# Sheet1.net
KiCad netlist of a schematic drawn in Altium Designer
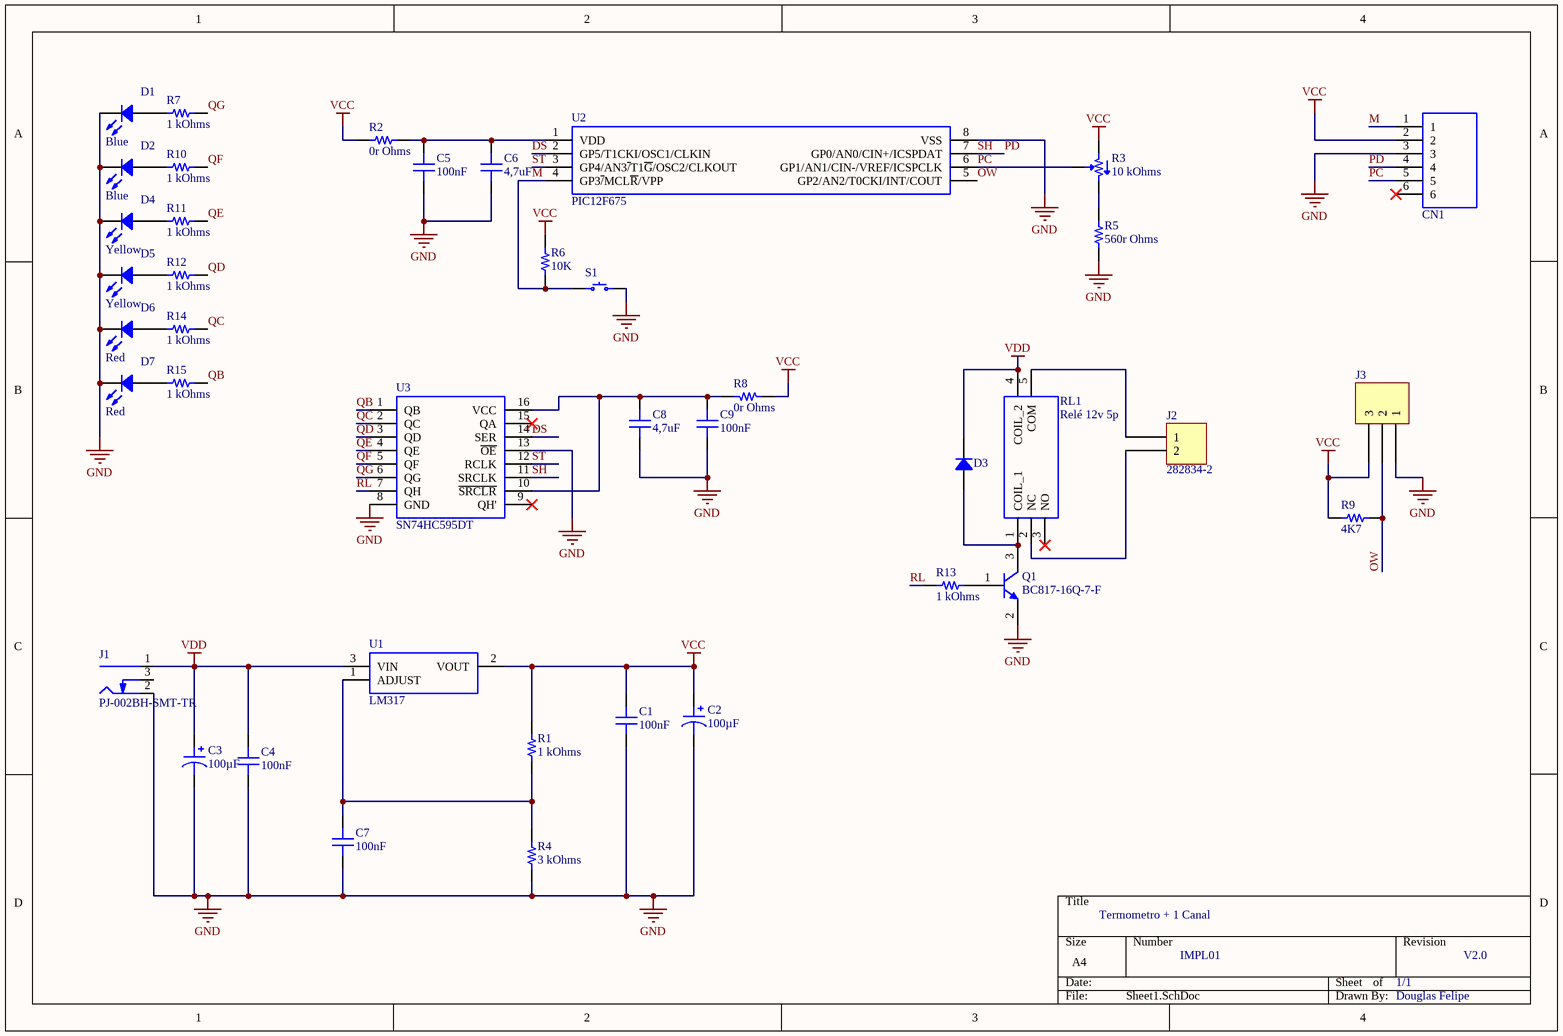
[diagram p0: Sheet1.SchDoc]

(export (version "E")
  (design (tool "Eeschema 10.0.6"))
  (components
    (comp (ref "C1")
      (value "100nF")
      (footprint "CAP 0805_2012")
      (description "CAP CER 100PF 200V C0G/NP0 0805")
      (fields (field (name "PART NUMBER") "08052A101JAT2A") (field (name "MANUFACTURER") "AVX Corporation"))
      (libsource (lib "Celestial Altium Library - altium_library") (part "Capacitor"))
    )
    (comp (ref "C2")
      (value "100µF")
      (footprint "CAP ALSMD 8.3MM H10.5MM")
      (description "CAP ALUM 22UF 20% 100V SMD")
      (fields (field (name "PART NUMBER") "100SEV22M8X10.5") (field (name "MANUFACTURER") "Rubycon"))
      (libsource (lib "Celestial Altium Library - altium_library") (part "Polarised Capacitor"))
    )
    (comp (ref "C3")
      (value "100µF")
      (footprint "CAP ALSMD 8.3MM H10.5MM")
      (description "CAP ALUM 22UF 20% 100V SMD")
      (fields (field (name "PART NUMBER") "100SEV22M8X10.5") (field (name "MANUFACTURER") "Rubycon"))
      (libsource (lib "Celestial Altium Library - altium_library") (part "Polarised Capacitor"))
    )
    (comp (ref "C4")
      (value "100nF")
      (footprint "CAP 0805_2012")
      (description "CAP CER 100PF 200V C0G/NP0 0805")
      (fields (field (name "PART NUMBER") "08052A101JAT2A") (field (name "MANUFACTURER") "AVX Corporation"))
      (libsource (lib "Celestial Altium Library - altium_library") (part "Capacitor"))
    )
    (comp (ref "C5")
      (value "100nF")
      (footprint "CAP 0805_2012")
      (description "CAP CER 100PF 200V C0G/NP0 0805")
      (fields (field (name "PART NUMBER") "08052A101JAT2A") (field (name "MANUFACTURER") "AVX Corporation"))
      (libsource (lib "Celestial Altium Library - altium_library") (part "Capacitor"))
    )
    (comp (ref "C6")
      (value "4,7uF")
      (footprint "CAP 0805_2012")
      (description "CAP CER 100PF 200V C0G/NP0 0805")
      (fields (field (name "PART NUMBER") "08052A101JAT2A") (field (name "MANUFACTURER") "AVX Corporation"))
      (libsource (lib "Celestial Altium Library - altium_library") (part "Capacitor"))
    )
    (comp (ref "C7")
      (value "100nF")
      (footprint "CAP 0805_2012")
      (description "CAP CER 100PF 200V C0G/NP0 0805")
      (fields (field (name "PART NUMBER") "08052A101JAT2A") (field (name "MANUFACTURER") "AVX Corporation"))
      (libsource (lib "Celestial Altium Library - altium_library") (part "Capacitor"))
    )
    (comp (ref "C8")
      (value "4,7uF")
      (footprint "CAP 0805_2012")
      (description "CAP CER 100PF 200V C0G/NP0 0805")
      (fields (field (name "PART NUMBER") "08052A101JAT2A") (field (name "MANUFACTURER") "AVX Corporation"))
      (libsource (lib "Celestial Altium Library - altium_library") (part "Capacitor"))
    )
    (comp (ref "C9")
      (value "100nF")
      (footprint "CAP 0805_2012")
      (description "CAP CER 100PF 200V C0G/NP0 0805")
      (fields (field (name "PART NUMBER") "08052A101JAT2A") (field (name "MANUFACTURER") "AVX Corporation"))
      (libsource (lib "Celestial Altium Library - altium_library") (part "Capacitor"))
    )
    (comp (ref "CN1")
      (value "KK 6vias")
      (footprint "KK6")
      (libsource (lib "Meus Components") (part "KK 6vias"))
    )
    (comp (ref "D1")
      (value "Blue")
      (footprint "LED 0805_2012 BLUE")
      (description "2.0(L)X1.3(W)X0.8(H) MM")
      (fields
        (field (name "PART NUMBER") "B1701NB--20D000114U1930")
        (field (name "MANUFACTURER") "Harvatek Corporation")
      )
      (libsource (lib "Celestial Altium Library - altium_library") (part "LED"))
    )
    (comp (ref "D2")
      (value "Blue")
      (footprint "LED 0805_2012 BLUE")
      (description "2.0(L)X1.3(W)X0.8(H) MM")
      (fields
        (field (name "PART NUMBER") "B1701NB--20D000114U1930")
        (field (name "MANUFACTURER") "Harvatek Corporation")
      )
      (libsource (lib "Celestial Altium Library - altium_library") (part "LED"))
    )
    (comp (ref "D3")
      (value "1N4148W-TP")
      (footprint "SOD-123")
      (description "DIODE GEN PURP 100V 150MA SOD123")
      (fields (field (name "MANUFACTURER") "Micro Commercial Co"))
      (libsource (lib "Celestial Altium Library - altium_library") (part "Diode"))
    )
    (comp (ref "D4")
      (value "Yellow")
      (footprint "LED 0805_2012 YELLOW")
      (description "LED YELLOW DIFFUSED 2SMD")
      (fields (field (name "PART NUMBER") "5975411407F") (field (name "MANUFACTURER") "Dialight"))
      (libsource (lib "Celestial Altium Library - altium_library") (part "LED"))
    )
    (comp (ref "D5")
      (value "Yellow")
      (footprint "LED 0805_2012 YELLOW")
      (description "LED YELLOW DIFFUSED 2SMD")
      (fields (field (name "PART NUMBER") "5975411407F") (field (name "MANUFACTURER") "Dialight"))
      (libsource (lib "Celestial Altium Library - altium_library") (part "LED"))
    )
    (comp (ref "D6")
      (value "Red")
      (footprint "LED 0805_2012 RED")
      (description "LED")
      (fields
        (field (name "PART NUMBER") "VFHV1112H-3BZ2B-TR")
        (field (name "MANUFACTURER") "Stanley Electric Co")
      )
      (libsource (lib "Celestial Altium Library - altium_library") (part "LED"))
    )
    (comp (ref "D7")
      (value "Red")
      (footprint "LED 0805_2012 RED")
      (description "LED")
      (fields
        (field (name "PART NUMBER") "VFHV1112H-3BZ2B-TR")
        (field (name "MANUFACTURER") "Stanley Electric Co")
      )
      (libsource (lib "Celestial Altium Library - altium_library") (part "LED"))
    )
    (comp (ref "J1")
      (value "PJ-002BH-SMT-TR")
      (footprint "CUI PJ-002BH-SMT-TR")
      (description "CONN PWR JACK 2.5X5.5MM SOLDER")
      (fields (field (name "MANUFACTURER") "CUI Devices"))
      (libsource (lib "Celestial Altium Library - altium_library") (part "Barrel Connector"))
    )
    (comp (ref "J2")
      (value "282834-2")
      (footprint "TE 282834-2")
      (description "TERM BLK 2P SIDE ENT 2.54MM PCB")
      (fields (field (name "MANUFACTURER") "TE Connectivity AMP Connectors") (field (name "VOLTAGE") "150V"))
      (libsource (lib "Celestial Altium Library - altium_library") (part "2 Pin"))
    )
    (comp (ref "J3")
      (value "0022272031")
      (footprint "MOLEX KK 0022272031")
      (description "CONN HEADER VERT 3POS 2.54MM")
      (fields (field (name "MANUFACTURER") "Molex"))
      (libsource (lib "Celestial Altium Library - altium_library") (part "3 Pin"))
    )
    (comp (ref "Q1")
      (value "BC817-16Q-7-F")
      (footprint "DIODES SOT-23-3")
      (description "TRANS NPN 45V 0.5A SOT23-3")
      (fields (field (name "MANUFACTURER") "Diodes Incorporated"))
      (libsource (lib "Celestial Altium Library - altium_library") (part "DIODES INC NPN SOT-23-3"))
    )
    (comp (ref "R1")
      (value "1 kOhms")
      (footprint "RES 0805_2012")
      (description "RES 1K OHM 0.1% 1/10W 0805")
      (fields
        (field (name "PART NUMBER") "RNCS0805BKE1K00")
        (field (name "MANUFACTURER") "Stackpole Electronics Inc")
      )
      (libsource (lib "Celestial Altium Library - altium_library") (part "Resistor"))
    )
    (comp (ref "R2")
      (value "0r Ohms")
      (footprint "RES 0805_2012")
      (description "RES 1K OHM 0.1% 1/10W 0805")
      (fields
        (field (name "PART NUMBER") "RNCS0805BKE1K00")
        (field (name "MANUFACTURER") "Stackpole Electronics Inc")
      )
      (libsource (lib "Celestial Altium Library - altium_library") (part "Resistor"))
    )
    (comp (ref "R3")
      (value "10 kOhms")
      (footprint "POT BOURNS TRIMPOT TC33")
      (description "TRIMMER 10K OHM 0.1W J LEAD TOP")
      (fields (field (name "PART NUMBER") "TC33X-1-103E") (field (name "MANUFACTURER") "Bourns Inc."))
      (libsource (lib "Celestial Altium Library - altium_library") (part "Potentiometer"))
    )
    (comp (ref "R4")
      (value "3 kOhms")
      (footprint "RES 0805_2012")
      (description "RES SMD 3K OHM 0.5% 1/8W 0805")
      (fields (field (name "PART NUMBER") "RT0805DRD073KL") (field (name "MANUFACTURER") "Yageo"))
      (libsource (lib "Celestial Altium Library - altium_library") (part "Resistor"))
    )
    (comp (ref "R5")
      (value "560r Ohms")
      (footprint "RES 0805_2012")
      (description "RES 1K OHM 0.1% 1/10W 0805")
      (fields
        (field (name "PART NUMBER") "RNCS0805BKE1K00")
        (field (name "MANUFACTURER") "Stackpole Electronics Inc")
      )
      (libsource (lib "Celestial Altium Library - altium_library") (part "Resistor"))
    )
    (comp (ref "R6")
      (value "10K")
      (footprint "RES 0805_2012")
      (description "RES 1K OHM 0.1% 1/10W 0805")
      (fields
        (field (name "PART NUMBER") "RNCS0805BKE1K00")
        (field (name "MANUFACTURER") "Stackpole Electronics Inc")
      )
      (libsource (lib "Celestial Altium Library - altium_library") (part "Resistor"))
    )
    (comp (ref "R7")
      (value "1 kOhms")
      (footprint "RES 0805_2012")
      (description "RES 1K OHM 0.1% 1/10W 0805")
      (fields
        (field (name "PART NUMBER") "RNCS0805BKE1K00")
        (field (name "MANUFACTURER") "Stackpole Electronics Inc")
      )
      (libsource (lib "Celestial Altium Library - altium_library") (part "Resistor"))
    )
    (comp (ref "R8")
      (value "0r Ohms")
      (footprint "RES 0805_2012")
      (description "RES 1K OHM 0.1% 1/10W 0805")
      (fields
        (field (name "PART NUMBER") "RNCS0805BKE1K00")
        (field (name "MANUFACTURER") "Stackpole Electronics Inc")
      )
      (libsource (lib "Celestial Altium Library - altium_library") (part "Resistor"))
    )
    (comp (ref "R9")
      (value "4K7")
      (footprint "RES 0805_2012")
      (description "RES 1K OHM 0.1% 1/10W 0805")
      (fields
        (field (name "PART NUMBER") "RNCS0805BKE1K00")
        (field (name "MANUFACTURER") "Stackpole Electronics Inc")
      )
      (libsource (lib "Celestial Altium Library - altium_library") (part "Resistor"))
    )
    (comp (ref "R10")
      (value "1 kOhms")
      (footprint "RES 0805_2012")
      (description "RES 1K OHM 0.1% 1/10W 0805")
      (fields
        (field (name "PART NUMBER") "RNCS0805BKE1K00")
        (field (name "MANUFACTURER") "Stackpole Electronics Inc")
      )
      (libsource (lib "Celestial Altium Library - altium_library") (part "Resistor"))
    )
    (comp (ref "R11")
      (value "1 kOhms")
      (footprint "RES 0805_2012")
      (description "RES 1K OHM 0.1% 1/10W 0805")
      (fields
        (field (name "PART NUMBER") "RNCS0805BKE1K00")
        (field (name "MANUFACTURER") "Stackpole Electronics Inc")
      )
      (libsource (lib "Celestial Altium Library - altium_library") (part "Resistor"))
    )
    (comp (ref "R12")
      (value "1 kOhms")
      (footprint "RES 0805_2012")
      (description "RES 1K OHM 0.1% 1/10W 0805")
      (fields
        (field (name "PART NUMBER") "RNCS0805BKE1K00")
        (field (name "MANUFACTURER") "Stackpole Electronics Inc")
      )
      (libsource (lib "Celestial Altium Library - altium_library") (part "Resistor"))
    )
    (comp (ref "R13")
      (value "1 kOhms")
      (footprint "RES 0805_2012")
      (description "RES 1K OHM 0.1% 1/10W 0805")
      (fields
        (field (name "PART NUMBER") "RNCS0805BKE1K00")
        (field (name "MANUFACTURER") "Stackpole Electronics Inc")
      )
      (libsource (lib "Celestial Altium Library - altium_library") (part "Resistor"))
    )
    (comp (ref "R14")
      (value "1 kOhms")
      (footprint "RES 0805_2012")
      (description "RES 1K OHM 0.1% 1/10W 0805")
      (fields
        (field (name "PART NUMBER") "RNCS0805BKE1K00")
        (field (name "MANUFACTURER") "Stackpole Electronics Inc")
      )
      (libsource (lib "Celestial Altium Library - altium_library") (part "Resistor"))
    )
    (comp (ref "R15")
      (value "1 kOhms")
      (footprint "RES 0805_2012")
      (description "RES 1K OHM 0.1% 1/10W 0805")
      (fields
        (field (name "PART NUMBER") "RNCS0805BKE1K00")
        (field (name "MANUFACTURER") "Stackpole Electronics Inc")
      )
      (libsource (lib "Celestial Altium Library - altium_library") (part "Resistor"))
    )
    (comp (ref "RL1")
      (value "Relé 12v 5p")
      (footprint "Relé SPDTPW")
      (libsource (lib "Meus Components") (part "Relé 12v 5p"))
    )
    (comp (ref "S1")
      (value "KXT341 LHS")
      (footprint "C&K KXT3")
      (description "SWITCH TACTILE SPST-NO 0.02A 15V")
      (fields (field (name "MANUFACTURER") "C&K"))
      (libsource (lib "Celestial Altium Library - altium_library") (part "SPST-NO 2 PIN"))
    )
    (comp (ref "U1") (value "LM317") (footprint "TO252-3") (libsource (lib "Meus Components") (part "LM317")))
    (comp (ref "U2")
      (value "PIC12F675")
      (footprint "SOIC8")
      (libsource (lib "Meus Components") (part "PIC12F675"))
    )
    (comp (ref "U3")
      (value "SN74HC595DT")
      (footprint "SOIC16")
      (libsource (lib "Meus Components") (part "SN74HC595DT"))
    )
  )
  (nets
    (net (code "1") (name "/DS") (class "Default")
      (node (ref "U2") (pin "2") (pinfunction "GP5/T1CKI/OSC1/CLKIN_2") (pintype "passive"))
      (node (ref "U3") (pin "14") (pinfunction "SER_14") (pintype "passive"))
    )
    (net (code "2") (name "/M") (class "Default")
      (node (ref "CN1") (pin "1") (pinfunction "1_1") (pintype "passive"))
      (node (ref "R6") (pin "1") (pinfunction "1_1") (pintype "passive"))
      (node (ref "S1") (pin "1") (pinfunction "1_1") (pintype "passive"))
      (node (ref "U2") (pin "4") (pinfunction "GP3~{/}MCL~{R}/VPP_4") (pintype "passive"))
    )
    (net (code "3") (name "/OW") (class "Default")
      (node (ref "J3") (pin "2") (pinfunction "2_2") (pintype "passive"))
      (node (ref "R9") (pin "1") (pinfunction "1_1") (pintype "passive"))
      (node (ref "U2") (pin "5") (pinfunction "GP2/AN2/T0CKI/INT/COUT_5") (pintype "passive"))
    )
    (net (code "4") (name "/PC") (class "Default")
      (node (ref "CN1") (pin "5") (pinfunction "5_5") (pintype "passive"))
      (node (ref "R3") (pin "2") (pinfunction "2_2") (pintype "passive"))
      (node (ref "U2") (pin "6") (pinfunction "GP1/AN1/CIN-/VREF/ICSPCLK_6") (pintype "passive"))
    )
    (net (code "5") (name "/PD") (class "Default")
      (node (ref "CN1") (pin "4") (pinfunction "4_4") (pintype "passive"))
      (node (ref "U2") (pin "7") (pinfunction "GP0/AN0/CIN+/ICSPDAT_7") (pintype "passive"))
      (node (ref "U3") (pin "11") (pinfunction "SRCLK_11") (pintype "passive"))
    )
    (net (code "6") (name "/QB") (class "Default")
      (node (ref "R15") (pin "1") (pinfunction "1_1") (pintype "passive"))
      (node (ref "U3") (pin "1") (pinfunction "QB_1") (pintype "passive"))
    )
    (net (code "7") (name "/QC") (class "Default")
      (node (ref "R14") (pin "1") (pinfunction "1_1") (pintype "passive"))
      (node (ref "U3") (pin "2") (pinfunction "QC_2") (pintype "passive"))
    )
    (net (code "8") (name "/QD") (class "Default")
      (node (ref "R12") (pin "1") (pinfunction "1_1") (pintype "passive"))
      (node (ref "U3") (pin "3") (pinfunction "QD_3") (pintype "passive"))
    )
    (net (code "9") (name "/QE") (class "Default")
      (node (ref "R11") (pin "1") (pinfunction "1_1") (pintype "passive"))
      (node (ref "U3") (pin "4") (pinfunction "QE_4") (pintype "passive"))
    )
    (net (code "10") (name "/QF") (class "Default")
      (node (ref "R10") (pin "1") (pinfunction "1_1") (pintype "passive"))
      (node (ref "U3") (pin "5") (pinfunction "QF_5") (pintype "passive"))
    )
    (net (code "11") (name "/QG") (class "Default")
      (node (ref "R7") (pin "1") (pinfunction "1_1") (pintype "passive"))
      (node (ref "U3") (pin "6") (pinfunction "QG_6") (pintype "passive"))
    )
    (net (code "12") (name "/RL") (class "Default")
      (node (ref "R13") (pin "2") (pinfunction "2_2") (pintype "passive"))
      (node (ref "U3") (pin "7") (pinfunction "QH_7") (pintype "passive"))
    )
    (net (code "13") (name "/ST") (class "Default")
      (node (ref "U2") (pin "3") (pinfunction "GP4/AN3~{/}T1~{G}/OSC2/CLKOUT_3") (pintype "passive"))
      (node (ref "U3") (pin "12") (pinfunction "RCLK_12") (pintype "passive"))
    )
    (net (code "14") (name "GND") (class "Default")
      (node (ref "C1") (pin "1") (pinfunction "1_1") (pintype "passive"))
      (node (ref "C2") (pin "2") (pinfunction "2_2") (pintype "passive"))
      (node (ref "C3") (pin "2") (pinfunction "2_2") (pintype "passive"))
      (node (ref "C4") (pin "1") (pinfunction "1_1") (pintype "passive"))
      (node (ref "C5") (pin "1") (pinfunction "1_1") (pintype "passive"))
      (node (ref "C6") (pin "1") (pinfunction "1_1") (pintype "passive"))
      (node (ref "C7") (pin "1") (pinfunction "1_1") (pintype "passive"))
      (node (ref "C8") (pin "1") (pinfunction "1_1") (pintype "passive"))
      (node (ref "C9") (pin "1") (pinfunction "1_1") (pintype "passive"))
      (node (ref "CN1") (pin "3") (pinfunction "3_3") (pintype "passive"))
      (node (ref "D1") (pin "2") (pinfunction "2_2") (pintype "passive"))
      (node (ref "D2") (pin "2") (pinfunction "2_2") (pintype "passive"))
      (node (ref "D4") (pin "2") (pinfunction "2_2") (pintype "passive"))
      (node (ref "D5") (pin "2") (pinfunction "2_2") (pintype "passive"))
      (node (ref "D6") (pin "2") (pinfunction "2_2") (pintype "passive"))
      (node (ref "D7") (pin "2") (pinfunction "2_2") (pintype "passive"))
      (node (ref "J1") (pin "2") (pinfunction "Outer_2") (pintype "passive"))
      (node (ref "J3") (pin "1") (pinfunction "1_1") (pintype "passive"))
      (node (ref "Q1") (pin "2") (pinfunction "E_2") (pintype "passive"))
      (node (ref "R4") (pin "1") (pinfunction "1_1") (pintype "passive"))
      (node (ref "R5") (pin "1") (pinfunction "1_1") (pintype "passive"))
      (node (ref "S1") (pin "2") (pinfunction "2_2") (pintype "passive"))
      (node (ref "U2") (pin "8") (pinfunction "VSS_8") (pintype "passive"))
      (node (ref "U3") (pin "13") (pinfunction "OE_13") (pintype "passive"))
      (node (ref "U3") (pin "8") (pinfunction "GND_8") (pintype "passive"))
    )
    (net (code "15") (name "Net-(D1-Pad1)") (class "Default")
      (node (ref "D1") (pin "1") (pinfunction "1_1") (pintype "passive"))
      (node (ref "R7") (pin "2") (pinfunction "2_2") (pintype "passive"))
    )
    (net (code "16") (name "Net-(D2-Pad1)") (class "Default")
      (node (ref "D2") (pin "1") (pinfunction "1_1") (pintype "passive"))
      (node (ref "R10") (pin "2") (pinfunction "2_2") (pintype "passive"))
    )
    (net (code "17") (name "Net-(D4-Pad1)") (class "Default")
      (node (ref "D4") (pin "1") (pinfunction "1_1") (pintype "passive"))
      (node (ref "R11") (pin "2") (pinfunction "2_2") (pintype "passive"))
    )
    (net (code "18") (name "Net-(D5-Pad1)") (class "Default")
      (node (ref "D5") (pin "1") (pinfunction "1_1") (pintype "passive"))
      (node (ref "R12") (pin "2") (pinfunction "2_2") (pintype "passive"))
    )
    (net (code "19") (name "Net-(D6-Pad1)") (class "Default")
      (node (ref "D6") (pin "1") (pinfunction "1_1") (pintype "passive"))
      (node (ref "R14") (pin "2") (pinfunction "2_2") (pintype "passive"))
    )
    (net (code "20") (name "Net-(D7-Pad1)") (class "Default")
      (node (ref "D7") (pin "1") (pinfunction "1_1") (pintype "passive"))
      (node (ref "R15") (pin "2") (pinfunction "2_2") (pintype "passive"))
    )
    (net (code "21") (name "Net-(Q1-B)") (class "Default")
      (node (ref "Q1") (pin "1") (pinfunction "B_1") (pintype "passive"))
      (node (ref "R13") (pin "1") (pinfunction "1_1") (pintype "passive"))
    )
    (net (code "22") (name "Net-(Q1-C)") (class "Default")
      (node (ref "D3") (pin "1") (pinfunction "1_1") (pintype "passive"))
      (node (ref "Q1") (pin "3") (pinfunction "C_3") (pintype "passive"))
      (node (ref "RL1") (pin "1") (pinfunction "COIL_1_1") (pintype "passive"))
    )
    (net (code "23") (name "Net-(R3-Pad3)") (class "Default")
      (node (ref "R3") (pin "3") (pinfunction "3_3") (pintype "passive"))
      (node (ref "R5") (pin "2") (pinfunction "2_2") (pintype "passive"))
    )
    (net (code "24") (name "Net-(RL1-COM)") (class "Default")
      (node (ref "J2") (pin "1") (pinfunction "1_1") (pintype "passive"))
      (node (ref "RL1") (pin "5") (pinfunction "COM_5") (pintype "passive"))
    )
    (net (code "25") (name "Net-(RL1-NC)") (class "Default")
      (node (ref "J2") (pin "2") (pinfunction "2_2") (pintype "passive"))
      (node (ref "RL1") (pin "2") (pinfunction "NC_2") (pintype "passive"))
    )
    (net (code "26") (name "Net-(U1-ADJUST)") (class "Default")
      (node (ref "C7") (pin "2") (pinfunction "2_2") (pintype "passive"))
      (node (ref "R1") (pin "1") (pinfunction "1_1") (pintype "passive"))
      (node (ref "R4") (pin "2") (pinfunction "2_2") (pintype "passive"))
      (node (ref "U1") (pin "1") (pinfunction "ADJUST_1") (pintype "passive"))
    )
    (net (code "27") (name "Net-(U2-VDD)") (class "Default")
      (node (ref "C5") (pin "2") (pinfunction "2_2") (pintype "passive"))
      (node (ref "C6") (pin "2") (pinfunction "2_2") (pintype "passive"))
      (node (ref "R2") (pin "1") (pinfunction "1_1") (pintype "passive"))
      (node (ref "U2") (pin "1") (pinfunction "VDD_1") (pintype "passive"))
    )
    (net (code "28") (name "Net-(U3-SRCLR)") (class "Default")
      (node (ref "C8") (pin "2") (pinfunction "2_2") (pintype "passive"))
      (node (ref "C9") (pin "2") (pinfunction "2_2") (pintype "passive"))
      (node (ref "R8") (pin "1") (pinfunction "1_1") (pintype "passive"))
      (node (ref "U3") (pin "10") (pinfunction "SRCLR_10") (pintype "passive"))
      (node (ref "U3") (pin "16") (pinfunction "VCC_16") (pintype "passive"))
    )
    (net (code "29") (name "VCC") (class "Default")
      (node (ref "C1") (pin "2") (pinfunction "2_2") (pintype "passive"))
      (node (ref "C2") (pin "1") (pinfunction "1_1") (pintype "passive"))
      (node (ref "CN1") (pin "2") (pinfunction "2_2") (pintype "passive"))
      (node (ref "J3") (pin "3") (pinfunction "3_3") (pintype "passive"))
      (node (ref "R1") (pin "2") (pinfunction "2_2") (pintype "passive"))
      (node (ref "R2") (pin "2") (pinfunction "2_2") (pintype "passive"))
      (node (ref "R3") (pin "1") (pinfunction "1_1") (pintype "passive"))
      (node (ref "R6") (pin "2") (pinfunction "2_2") (pintype "passive"))
      (node (ref "R8") (pin "2") (pinfunction "2_2") (pintype "passive"))
      (node (ref "R9") (pin "2") (pinfunction "2_2") (pintype "passive"))
      (node (ref "U1") (pin "2") (pinfunction "VOUT_2") (pintype "passive"))
    )
    (net (code "30") (name "VDD") (class "Default")
      (node (ref "C3") (pin "1") (pinfunction "1_1") (pintype "passive"))
      (node (ref "C4") (pin "2") (pinfunction "2_2") (pintype "passive"))
      (node (ref "D3") (pin "2") (pinfunction "2_2") (pintype "passive"))
      (node (ref "J1") (pin "1") (pinfunction "Centre_1") (pintype "passive"))
      (node (ref "RL1") (pin "4") (pinfunction "COIL_2_4") (pintype "passive"))
      (node (ref "U1") (pin "3") (pinfunction "VIN_3") (pintype "passive"))
    )
    (net (code "31") (name "unconnected-(CN1-Pad6)") (class "Default")
      (node (ref "CN1") (pin "6") (pinfunction "6_6") (pintype "passive+no_connect"))
    )
    (net (code "32") (name "unconnected-(J1-SW-Pad3)") (class "Default")
      (node (ref "J1") (pin "3") (pinfunction "SW_3") (pintype "passive"))
    )
    (net (code "33") (name "unconnected-(RL1-NO-Pad3)") (class "Default")
      (node (ref "RL1") (pin "3") (pinfunction "NO_3") (pintype "passive+no_connect"))
    )
    (net (code "34") (name "unconnected-(U3-QA-Pad15)") (class "Default")
      (node (ref "U3") (pin "15") (pinfunction "QA_15") (pintype "passive+no_connect"))
    )
    (net (code "35") (name "unconnected-(U3-QH'-Pad9)") (class "Default")
      (node (ref "U3") (pin "9") (pinfunction "QH'_9") (pintype "passive+no_connect"))
    )
  )
)
